# Encoders.net
KiCad netlist of a schematic drawn in Altium Designer
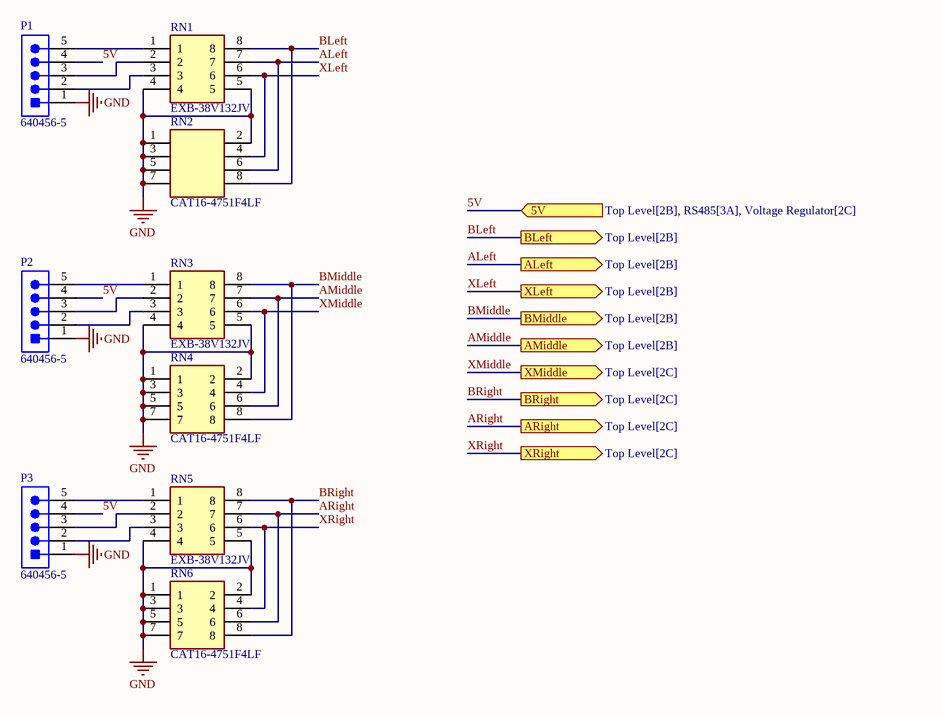
[diagram p0: Encoders.SchDoc]

(export (version "E")
  (design (tool "Eeschema 10.0.6"))
  (components
    (comp (ref "P1")
      (value "640456-5")
      (footprint "TECO-640456-5")
      (fields (field (name "MANUFACTURER") "TE Connectivity"))
      (libsource (lib "Altium Content Vault") (part "CN-1P-M-R5"))
    )
    (comp (ref "P2")
      (value "640456-5")
      (footprint "TECO-640456-5")
      (fields (field (name "MANUFACTURER") "TE Connectivity"))
      (libsource (lib "Altium Content Vault") (part "CN-1P-M-R5"))
    )
    (comp (ref "P3")
      (value "640456-5")
      (footprint "TECO-640456-5")
      (fields (field (name "MANUFACTURER") "TE Connectivity"))
      (libsource (lib "Altium Content Vault") (part "CN-1P-M-R5"))
    )
    (comp (ref "RN1")
      (value "EXB-38V132JV")
      (footprint "SamacSys:EXB38V132JV")
      (description "Resistor Network")
      (fields (field (name "MOUSER PART NUMBER") "667-EXB-38V132JV"))
      (libsource (lib "*") (part "EXB-38V132JV"))
    )
    (comp (ref "RN2")
      (value "CAT16-4751F4LF")
      (footprint "SamacSys:CAPCAV80P155X320X60-8L")
      (description "Resistor Network")
      (fields (field (name "MOUSER PART NUMBER") "652-CAT16-4751F4LF"))
      (libsource (lib "*") (part "CAT16-4751F4LF"))
    )
    (comp (ref "RN3")
      (value "EXB-38V132JV")
      (footprint "SamacSys:EXB38V132JV")
      (description "Resistor Network")
      (fields (field (name "MOUSER PART NUMBER") "667-EXB-38V132JV"))
      (libsource (lib "*") (part "EXB-38V132JV"))
    )
    (comp (ref "RN4")
      (value "CAT16-4751F4LF")
      (footprint "SamacSys:CAPCAV80P155X320X60-8L")
      (description "Resistor Network")
      (fields (field (name "MOUSER PART NUMBER") "652-CAT16-4751F4LF"))
      (libsource (lib "SamacSys") (part "CAT16-4751F4LF"))
    )
    (comp (ref "RN5")
      (value "EXB-38V132JV")
      (footprint "SamacSys:EXB38V132JV")
      (description "Resistor Network")
      (fields (field (name "MOUSER PART NUMBER") "667-EXB-38V132JV"))
      (libsource (lib "*") (part "EXB-38V132JV"))
    )
    (comp (ref "RN6")
      (value "CAT16-4751F4LF")
      (footprint "CAPCAV80P155X320X60-8L")
      (description "Resistor Network")
      (fields (field (name "MOUSER PART NUMBER") "652-CAT16-4751F4LF"))
      (libsource (lib "SamacSys") (part "CAT16-4751F4LF"))
    )
  )
  (nets
    (net (code "1") (name "/5V") (class "Default")
      (node (ref "P1") (pin "4") (pinfunction "VCC_4") (pintype "passive"))
      (node (ref "P2") (pin "4") (pinfunction "VCC_4") (pintype "passive"))
      (node (ref "P3") (pin "4") (pinfunction "VCC_4") (pintype "passive"))
    )
    (net (code "2") (name "/ALeft") (class "Default")
      (node (ref "RN1") (pin "7") (pinfunction "7_7") (pintype "passive"))
      (node (ref "RN2") (pin "6") (pinfunction "6_6") (pintype "passive"))
    )
    (net (code "3") (name "/AMiddle") (class "Default")
      (node (ref "RN3") (pin "7") (pinfunction "7_7") (pintype "passive"))
      (node (ref "RN4") (pin "6") (pinfunction "6_6") (pintype "passive"))
    )
    (net (code "4") (name "/ARight") (class "Default")
      (node (ref "RN5") (pin "7") (pinfunction "7_7") (pintype "passive"))
      (node (ref "RN6") (pin "6") (pinfunction "6_6") (pintype "passive"))
    )
    (net (code "5") (name "/BLeft") (class "Default")
      (node (ref "RN1") (pin "8") (pinfunction "8_8") (pintype "passive"))
      (node (ref "RN2") (pin "8") (pinfunction "8_8") (pintype "passive"))
    )
    (net (code "6") (name "/BMiddle") (class "Default")
      (node (ref "RN3") (pin "8") (pinfunction "8_8") (pintype "passive"))
      (node (ref "RN4") (pin "8") (pinfunction "8_8") (pintype "passive"))
    )
    (net (code "7") (name "/BRight") (class "Default")
      (node (ref "RN5") (pin "8") (pinfunction "8_8") (pintype "passive"))
      (node (ref "RN6") (pin "8") (pinfunction "8_8") (pintype "passive"))
    )
    (net (code "8") (name "/XLeft") (class "Default")
      (node (ref "RN1") (pin "6") (pinfunction "6_6") (pintype "passive"))
      (node (ref "RN2") (pin "4") (pinfunction "4_4") (pintype "passive"))
    )
    (net (code "9") (name "/XMiddle") (class "Default")
      (node (ref "RN3") (pin "6") (pinfunction "6_6") (pintype "passive"))
      (node (ref "RN4") (pin "4") (pinfunction "4_4") (pintype "passive"))
    )
    (net (code "10") (name "/XRight") (class "Default")
      (node (ref "RN5") (pin "6") (pinfunction "6_6") (pintype "passive"))
      (node (ref "RN6") (pin "4") (pinfunction "4_4") (pintype "passive"))
    )
    (net (code "11") (name "GND") (class "Default")
      (node (ref "P1") (pin "1") (pinfunction "DTR_1") (pintype "passive"))
      (node (ref "P2") (pin "1") (pinfunction "DTR_1") (pintype "passive"))
      (node (ref "P3") (pin "1") (pinfunction "DTR_1") (pintype "passive"))
      (node (ref "RN1") (pin "4") (pinfunction "4_4") (pintype "passive"))
      (node (ref "RN1") (pin "5") (pinfunction "5_5") (pintype "passive"))
      (node (ref "RN2") (pin "1") (pinfunction "1_1") (pintype "passive"))
      (node (ref "RN2") (pin "2") (pinfunction "2_2") (pintype "passive"))
      (node (ref "RN2") (pin "3") (pinfunction "3_3") (pintype "passive"))
      (node (ref "RN2") (pin "5") (pinfunction "5_5") (pintype "passive"))
      (node (ref "RN2") (pin "7") (pinfunction "7_7") (pintype "passive"))
      (node (ref "RN3") (pin "4") (pinfunction "4_4") (pintype "passive"))
      (node (ref "RN3") (pin "5") (pinfunction "5_5") (pintype "passive"))
      (node (ref "RN4") (pin "1") (pinfunction "1_1") (pintype "passive"))
      (node (ref "RN4") (pin "2") (pinfunction "2_2") (pintype "passive"))
      (node (ref "RN4") (pin "3") (pinfunction "3_3") (pintype "passive"))
      (node (ref "RN4") (pin "5") (pinfunction "5_5") (pintype "passive"))
      (node (ref "RN4") (pin "7") (pinfunction "7_7") (pintype "passive"))
      (node (ref "RN5") (pin "4") (pinfunction "4_4") (pintype "passive"))
      (node (ref "RN5") (pin "5") (pinfunction "5_5") (pintype "passive"))
      (node (ref "RN6") (pin "1") (pinfunction "1_1") (pintype "passive"))
      (node (ref "RN6") (pin "2") (pinfunction "2_2") (pintype "passive"))
      (node (ref "RN6") (pin "3") (pinfunction "3_3") (pintype "passive"))
      (node (ref "RN6") (pin "5") (pinfunction "5_5") (pintype "passive"))
      (node (ref "RN6") (pin "7") (pinfunction "7_7") (pintype "passive"))
    )
    (net (code "12") (name "Net-(P1-CTS)") (class "Default")
      (node (ref "P1") (pin "5") (pinfunction "CTS_5") (pintype "passive"))
      (node (ref "RN1") (pin "1") (pinfunction "1_1") (pintype "passive"))
    )
    (net (code "13") (name "Net-(P1-RXI)") (class "Default")
      (node (ref "P1") (pin "2") (pinfunction "RXI_2") (pintype "passive"))
      (node (ref "RN1") (pin "3") (pinfunction "3_3") (pintype "passive"))
    )
    (net (code "14") (name "Net-(P1-TXO)") (class "Default")
      (node (ref "P1") (pin "3") (pinfunction "TXO_3") (pintype "passive"))
      (node (ref "RN1") (pin "2") (pinfunction "2_2") (pintype "passive"))
    )
    (net (code "15") (name "Net-(P2-CTS)") (class "Default")
      (node (ref "P2") (pin "5") (pinfunction "CTS_5") (pintype "passive"))
      (node (ref "RN3") (pin "1") (pinfunction "1_1") (pintype "passive"))
    )
    (net (code "16") (name "Net-(P2-RXI)") (class "Default")
      (node (ref "P2") (pin "2") (pinfunction "RXI_2") (pintype "passive"))
      (node (ref "RN3") (pin "3") (pinfunction "3_3") (pintype "passive"))
    )
    (net (code "17") (name "Net-(P2-TXO)") (class "Default")
      (node (ref "P2") (pin "3") (pinfunction "TXO_3") (pintype "passive"))
      (node (ref "RN3") (pin "2") (pinfunction "2_2") (pintype "passive"))
    )
    (net (code "18") (name "Net-(P3-CTS)") (class "Default")
      (node (ref "P3") (pin "5") (pinfunction "CTS_5") (pintype "passive"))
      (node (ref "RN5") (pin "1") (pinfunction "1_1") (pintype "passive"))
    )
    (net (code "19") (name "Net-(P3-RXI)") (class "Default")
      (node (ref "P3") (pin "2") (pinfunction "RXI_2") (pintype "passive"))
      (node (ref "RN5") (pin "3") (pinfunction "3_3") (pintype "passive"))
    )
    (net (code "20") (name "Net-(P3-TXO)") (class "Default")
      (node (ref "P3") (pin "3") (pinfunction "TXO_3") (pintype "passive"))
      (node (ref "RN5") (pin "2") (pinfunction "2_2") (pintype "passive"))
    )
  )
)
